# wifi.net
KiCad netlist of a schematic drawn in Altium Designer
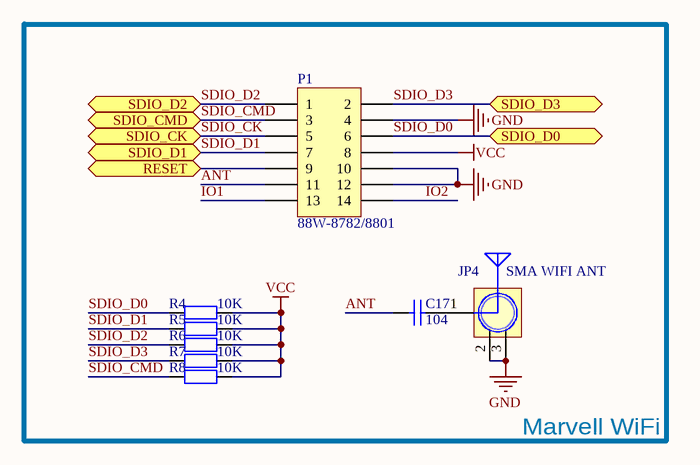
[diagram p0: wifi.SchDoc]

(export (version "E")
  (design (tool "Eeschema 10.0.6"))
  (components
    (comp (ref "C17")
      (value "104")
      (footprint "C 0603_L")
      (description "Capacitor")
      (fields (field (name "PUBLISHER") "Altium Limited"))
      (libsource (lib "Miscellaneous Devices") (part "Cap"))
    )
    (comp (ref "JP4")
      (value "SMA WIFI ANT")
      (footprint "SMA_FR")
      (description "SMA-2.4G射频天线接口")
      (fields (field (name "版权归属") "源创客"))
      (libsource (lib "14.1 - 天线") (part "SMA"))
    )
    (comp (ref "P1")
      (value "88W-8782/8801")
      (footprint "W8782_MODULE")
      (description "Header, 7-Pin, Dual row")
      (fields (field (name "PUBLISHER") "Altium Limited"))
      (libsource (lib "Miscellaneous Connectors") (part "Header 7X2"))
    )
    (comp (ref "R4")
      (value "10K")
      (footprint "R 0603_L")
      (description "Resistor")
      (fields (field (name "PUBLISHER") "Altium Limited"))
      (libsource (lib "") (part "Res2_1"))
    )
    (comp (ref "R5")
      (value "10K")
      (footprint "R 0603_L")
      (description "Resistor")
      (fields (field (name "PUBLISHER") "Altium Limited"))
      (libsource (lib "Miscellaneous Devices") (part "Res2"))
    )
    (comp (ref "R6")
      (value "10K")
      (footprint "R 0603_L")
      (description "Resistor")
      (fields (field (name "PUBLISHER") "Altium Limited"))
      (libsource (lib "Miscellaneous Devices") (part "Res2"))
    )
    (comp (ref "R7")
      (value "10K")
      (footprint "R 0603_L")
      (description "Resistor")
      (fields (field (name "PUBLISHER") "Altium Limited"))
      (libsource (lib "Miscellaneous Devices") (part "Res2"))
    )
    (comp (ref "R8")
      (value "10K")
      (footprint "R 0603_L")
      (description "Resistor")
      (fields (field (name "PUBLISHER") "Altium Limited"))
      (libsource (lib "Miscellaneous Devices") (part "Res2"))
    )
  )
  (nets
    (net (code "1") (name "/ANT") (class "Default")
      (node (ref "C17") (pin "2") (pinfunction "2_2") (pintype "passive"))
      (node (ref "P1") (pin "11") (pinfunction "11_11") (pintype "passive"))
    )
    (net (code "2") (name "/IO1") (class "Default")
      (node (ref "P1") (pin "13") (pinfunction "13_13") (pintype "passive"))
    )
    (net (code "3") (name "/IO2") (class "Default")
      (node (ref "P1") (pin "14") (pinfunction "14_14") (pintype "passive"))
    )
    (net (code "4") (name "/RESET") (class "Default")
      (node (ref "P1") (pin "9") (pinfunction "9_9") (pintype "passive"))
    )
    (net (code "5") (name "/SDIO_CK") (class "Default")
      (node (ref "P1") (pin "5") (pinfunction "5_5") (pintype "passive"))
    )
    (net (code "6") (name "/SDIO_CMD") (class "Default")
      (node (ref "P1") (pin "3") (pinfunction "3_3") (pintype "passive"))
      (node (ref "R8") (pin "1") (pinfunction "1_1") (pintype "passive"))
    )
    (net (code "7") (name "/SDIO_D0") (class "Default")
      (node (ref "P1") (pin "6") (pinfunction "6_6") (pintype "passive"))
      (node (ref "R4") (pin "2") (pinfunction "2_2") (pintype "passive"))
    )
    (net (code "8") (name "/SDIO_D1") (class "Default")
      (node (ref "P1") (pin "7") (pinfunction "7_7") (pintype "passive"))
      (node (ref "R5") (pin "1") (pinfunction "1_1") (pintype "passive"))
    )
    (net (code "9") (name "/SDIO_D2") (class "Default")
      (node (ref "P1") (pin "1") (pinfunction "1_1") (pintype "passive"))
      (node (ref "R6") (pin "1") (pinfunction "1_1") (pintype "passive"))
    )
    (net (code "10") (name "/SDIO_D3") (class "Default")
      (node (ref "P1") (pin "2") (pinfunction "2_2") (pintype "passive"))
      (node (ref "R7") (pin "1") (pinfunction "1_1") (pintype "passive"))
    )
    (net (code "11") (name "GND") (class "Default")
      (node (ref "JP4") (pin "2") (pinfunction "GND_2") (pintype "passive"))
      (node (ref "JP4") (pin "3") (pinfunction "GND_3") (pintype "passive"))
      (node (ref "P1") (pin "10") (pinfunction "10_10") (pintype "passive"))
      (node (ref "P1") (pin "12") (pinfunction "12_12") (pintype "passive"))
      (node (ref "P1") (pin "4") (pinfunction "4_4") (pintype "passive"))
    )
    (net (code "12") (name "Net-(JP4-ANT)") (class "Default")
      (node (ref "C17") (pin "1") (pinfunction "1_1") (pintype "passive"))
      (node (ref "JP4") (pin "1") (pinfunction "ANT_1") (pintype "passive"))
    )
    (net (code "13") (name "VCC") (class "Default")
      (node (ref "P1") (pin "8") (pinfunction "8_8") (pintype "passive"))
      (node (ref "R4") (pin "1") (pinfunction "1_1") (pintype "passive"))
      (node (ref "R5") (pin "2") (pinfunction "2_2") (pintype "passive"))
      (node (ref "R6") (pin "2") (pinfunction "2_2") (pintype "passive"))
      (node (ref "R7") (pin "2") (pinfunction "2_2") (pintype "passive"))
      (node (ref "R8") (pin "2") (pinfunction "2_2") (pintype "passive"))
    )
  )
)
